# Main.net
KiCad netlist of a schematic drawn in Altium Designer
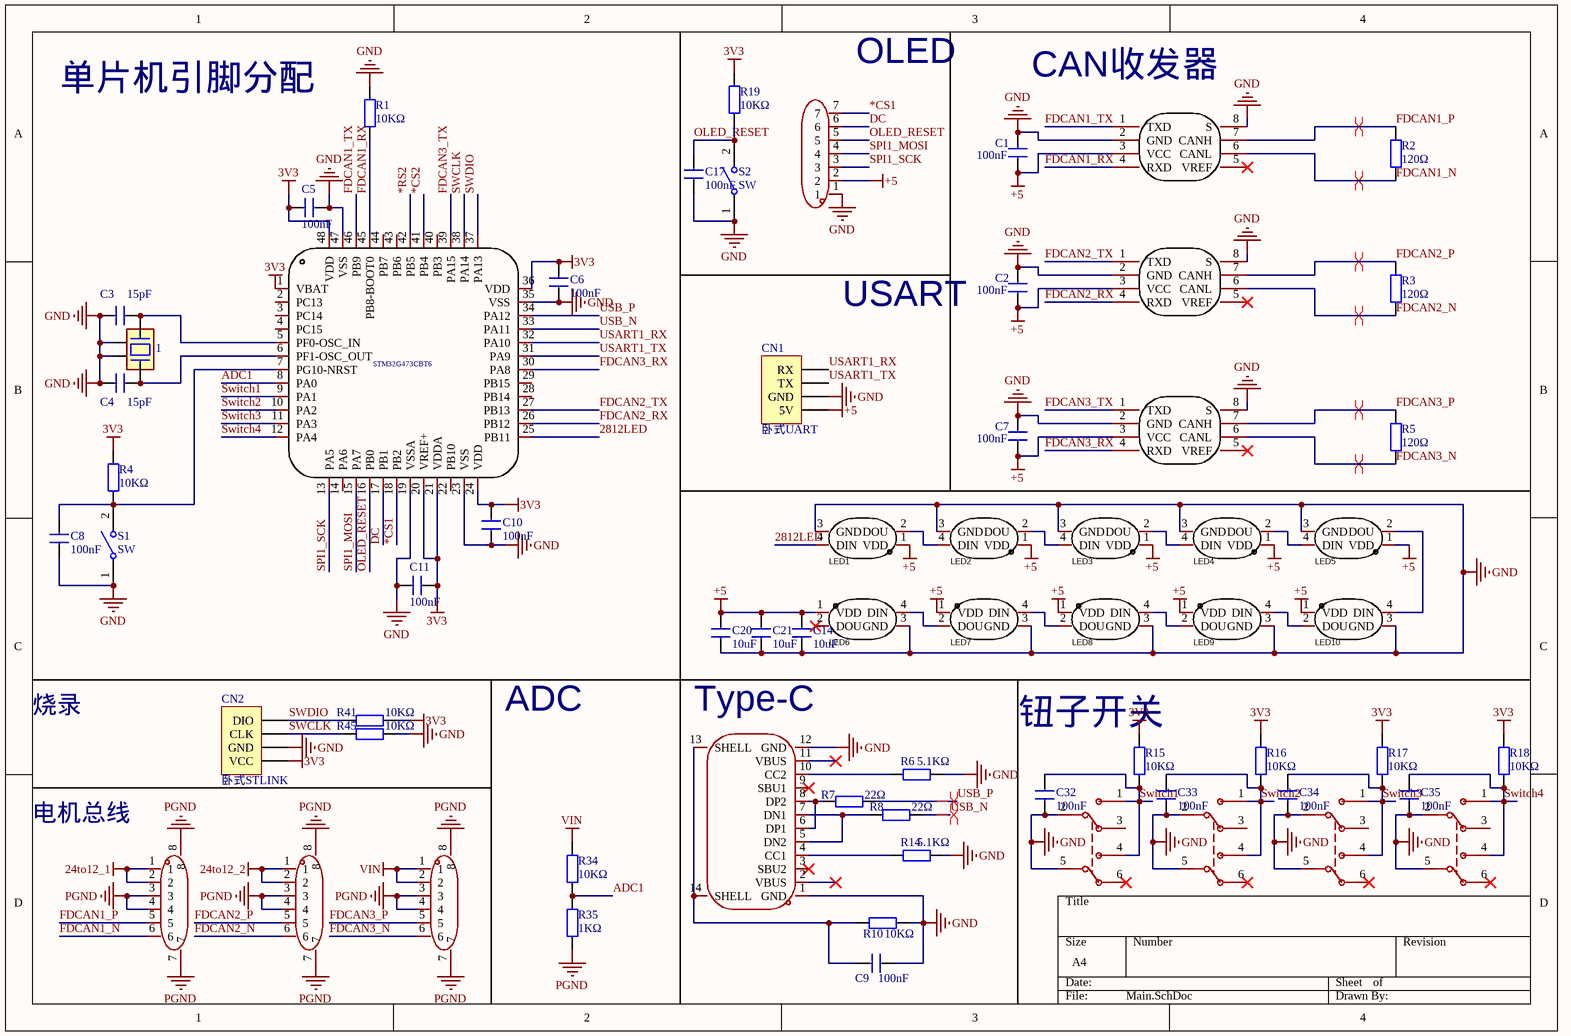
[diagram p0: Main.SchDoc]

(export (version "E")
  (design (tool "Eeschema 10.0.6"))
  (components
    (comp (ref "1")
      (value "3225贴片晶振")
      (footprint "OSC-3225-4P")
      (libsource (lib "Integrated_Library1") (part "3225贴片晶振"))
    )
    (comp (ref "C1")
      (value "100nF")
      (footprint "c0402")
      (description "贴片电容0402")
      (libsource (lib "Integrated_Library1") (part "0402贴片电容"))
    )
    (comp (ref "C2")
      (value "100nF")
      (footprint "c0402")
      (description "贴片电容0402")
      (libsource (lib "Integrated_Library1") (part "0402贴片电容"))
    )
    (comp (ref "C3")
      (value "15pF")
      (footprint "c0402")
      (description "贴片电容0402")
      (libsource (lib "Integrated_Library1") (part "0402贴片电容"))
    )
    (comp (ref "C4")
      (value "15pF")
      (footprint "c0402")
      (description "贴片电容0402")
      (libsource (lib "Integrated_Library1") (part "0402贴片电容"))
    )
    (comp (ref "C5")
      (value "100nF")
      (footprint "c0402")
      (description "贴片电容0402")
      (libsource (lib "Integrated_Library1") (part "0402贴片电容"))
    )
    (comp (ref "C6")
      (value "100nF")
      (footprint "c0402")
      (description "贴片电容0402")
      (libsource (lib "Integrated_Library1") (part "0402贴片电容"))
    )
    (comp (ref "C7")
      (value "100nF")
      (footprint "c0402")
      (description "贴片电容0402")
      (libsource (lib "Integrated_Library1") (part "0402贴片电容"))
    )
    (comp (ref "C8")
      (value "100nF")
      (footprint "c0402")
      (description "贴片电容0402")
      (libsource (lib "Integrated_Library1") (part "0402贴片电容"))
    )
    (comp (ref "C9")
      (value "100nF")
      (footprint "c0402")
      (description "贴片电容0402")
      (libsource (lib "Integrated_Library1") (part "0402贴片电容"))
    )
    (comp (ref "C10")
      (value "100nF")
      (footprint "c0402")
      (description "贴片电容0402")
      (libsource (lib "Integrated_Library1") (part "0402贴片电容"))
    )
    (comp (ref "C11")
      (value "100nF")
      (footprint "c0402")
      (description "贴片电容0402")
      (libsource (lib "Integrated_Library1") (part "0402贴片电容"))
    )
    (comp (ref "C14")
      (value "10uF")
      (footprint "1210")
      (description "1210贴片电容")
      (libsource (lib "Integrated_Library1") (part "1210贴片电容"))
    )
    (comp (ref "C17")
      (value "100nF")
      (footprint "c0402")
      (description "贴片电容0402")
      (libsource (lib "Integrated_Library1") (part "0402贴片电容"))
    )
    (comp (ref "C20")
      (value "10uF")
      (footprint "1210")
      (description "1210贴片电容")
      (libsource (lib "Integrated_Library1") (part "1210贴片电容"))
    )
    (comp (ref "C21")
      (value "10uF")
      (footprint "1210")
      (description "1210贴片电容")
      (libsource (lib "Integrated_Library1") (part "1210贴片电容"))
    )
    (comp (ref "C32")
      (value "100nF")
      (footprint "c0402")
      (description "贴片电容0402")
      (libsource (lib "Integrated_Library1") (part "0402贴片电容"))
    )
    (comp (ref "C33")
      (value "100nF")
      (footprint "c0402")
      (description "贴片电容0402")
      (libsource (lib "Integrated_Library1") (part "0402贴片电容"))
    )
    (comp (ref "C34")
      (value "100nF")
      (footprint "c0402")
      (description "贴片电容0402")
      (libsource (lib "Integrated_Library1") (part "0402贴片电容"))
    )
    (comp (ref "C35")
      (value "100nF")
      (footprint "c0402")
      (description "贴片电容0402")
      (libsource (lib "Integrated_Library1") (part "0402贴片电容"))
    )
    (comp (ref "CN1")
      (value "卧式UART")
      (footprint "CONN-SMD_4P-P1.25_GH1.25-4P")
      (libsource (lib "Integrated_Library1") (part "卧式UART"))
    )
    (comp (ref "CN2")
      (value "卧式STLINK")
      (footprint "CONN-SMD_4P-P1.25_GH1.25-4P")
      (libsource (lib "Integrated_Library1") (part "卧式STLINK"))
    )
    (comp (ref "H1")
      (value "PM254V-11-07-H85")
      (footprint "HDR-TH_7P-P2.54-V-F")
      (fields (field (name "MANUFACTURER") "XFCN(兴飞)"))
      (libsource (lib "Schlib1") (part "PM254V-11-07-H85"))
    )
    (comp (ref "LED1")
      (value "XL-5050RGBC-WS2812B")
      (footprint "LED-SMD_4P-L5.0-W5.0-BL_XL-5050RGBC")
      (description "WS2812B彩灯珠")
      (fields (field (name "MANUFACTURER") "XINGLIGHT(成兴光)"))
      (libsource (lib "RoBoMaster_AllComponent") (part "WS2812B彩灯珠"))
    )
    (comp (ref "LED2")
      (value "XL-5050RGBC-WS2812B")
      (footprint "LED-SMD_4P-L5.0-W5.0-BL_XL-5050RGBC")
      (description "WS2812B彩灯珠")
      (fields (field (name "MANUFACTURER") "XINGLIGHT(成兴光)"))
      (libsource (lib "RoBoMaster_AllComponent") (part "WS2812B彩灯珠"))
    )
    (comp (ref "LED3")
      (value "XL-5050RGBC-WS2812B")
      (footprint "LED-SMD_4P-L5.0-W5.0-BL_XL-5050RGBC")
      (description "WS2812B彩灯珠")
      (fields (field (name "MANUFACTURER") "XINGLIGHT(成兴光)"))
      (libsource (lib "RoBoMaster_AllComponent") (part "WS2812B彩灯珠"))
    )
    (comp (ref "LED4")
      (value "XL-5050RGBC-WS2812B")
      (footprint "LED-SMD_4P-L5.0-W5.0-BL_XL-5050RGBC")
      (description "WS2812B彩灯珠")
      (fields (field (name "MANUFACTURER") "XINGLIGHT(成兴光)"))
      (libsource (lib "RoBoMaster_AllComponent") (part "WS2812B彩灯珠"))
    )
    (comp (ref "LED5")
      (value "XL-5050RGBC-WS2812B")
      (footprint "LED-SMD_4P-L5.0-W5.0-BL_XL-5050RGBC")
      (description "WS2812B彩灯珠")
      (fields (field (name "MANUFACTURER") "XINGLIGHT(成兴光)"))
      (libsource (lib "RoBoMaster_AllComponent") (part "WS2812B彩灯珠"))
    )
    (comp (ref "LED6")
      (value "XL-5050RGBC-WS2812B")
      (footprint "LED-SMD_4P-L5.0-W5.0-BL_XL-5050RGBC")
      (description "WS2812B彩灯珠")
      (fields (field (name "MANUFACTURER") "XINGLIGHT(成兴光)"))
      (libsource (lib "RoBoMaster_AllComponent") (part "WS2812B彩灯珠"))
    )
    (comp (ref "LED7")
      (value "XL-5050RGBC-WS2812B")
      (footprint "LED-SMD_4P-L5.0-W5.0-BL_XL-5050RGBC")
      (description "WS2812B彩灯珠")
      (fields (field (name "MANUFACTURER") "XINGLIGHT(成兴光)"))
      (libsource (lib "RoBoMaster_AllComponent") (part "WS2812B彩灯珠"))
    )
    (comp (ref "LED8")
      (value "XL-5050RGBC-WS2812B")
      (footprint "LED-SMD_4P-L5.0-W5.0-BL_XL-5050RGBC")
      (description "WS2812B彩灯珠")
      (fields (field (name "MANUFACTURER") "XINGLIGHT(成兴光)"))
      (libsource (lib "RoBoMaster_AllComponent") (part "WS2812B彩灯珠"))
    )
    (comp (ref "LED9")
      (value "XL-5050RGBC-WS2812B")
      (footprint "LED-SMD_4P-L5.0-W5.0-BL_XL-5050RGBC")
      (description "WS2812B彩灯珠")
      (fields (field (name "MANUFACTURER") "XINGLIGHT(成兴光)"))
      (libsource (lib "RoBoMaster_AllComponent") (part "WS2812B彩灯珠"))
    )
    (comp (ref "LED10")
      (value "XL-5050RGBC-WS2812B")
      (footprint "LED-SMD_4P-L5.0-W5.0-BL_XL-5050RGBC")
      (description "WS2812B彩灯珠")
      (fields (field (name "MANUFACTURER") "XINGLIGHT(成兴光)"))
      (libsource (lib "RoBoMaster_AllComponent") (part "WS2812B彩灯珠"))
    )
    (comp (ref "R1")
      (value "10KΩ")
      (footprint "R0402")
      (description "0402贴片电阻")
      (libsource (lib "") (part "0402贴片电阻_3"))
    )
    (comp (ref "R2")
      (value "120Ω")
      (footprint "R0402")
      (description "0402贴片电阻")
      (libsource (lib "") (part "0402贴片电阻_1"))
    )
    (comp (ref "R3")
      (value "120Ω")
      (footprint "R0402")
      (description "0402贴片电阻")
      (libsource (lib "") (part "0402贴片电阻_1"))
    )
    (comp (ref "R4")
      (value "10KΩ")
      (footprint "R0402")
      (description "0402贴片电阻")
      (libsource (lib "") (part "0402贴片电阻_1"))
    )
    (comp (ref "R5")
      (value "120Ω")
      (footprint "R0402")
      (description "0402贴片电阻")
      (libsource (lib "") (part "0402贴片电阻_1"))
    )
    (comp (ref "R6")
      (value "5.1KΩ")
      (footprint "R0402")
      (description "0402贴片电阻")
      (libsource (lib "Integrated_Library1") (part "0402贴片电阻"))
    )
    (comp (ref "R7")
      (value "22Ω")
      (footprint "R0402")
      (description "0402贴片电阻")
      (libsource (lib "Integrated_Library1") (part "0402贴片电阻"))
    )
    (comp (ref "R8")
      (value "22Ω")
      (footprint "R0402")
      (description "0402贴片电阻")
      (libsource (lib "Integrated_Library1") (part "0402贴片电阻"))
    )
    (comp (ref "R10")
      (value "10KΩ")
      (footprint "R0402")
      (description "0402贴片电阻")
      (libsource (lib "Integrated_Library1") (part "0402贴片电阻"))
    )
    (comp (ref "R14")
      (value "5.1KΩ")
      (footprint "R0402")
      (description "0402贴片电阻")
      (libsource (lib "Integrated_Library1") (part "0402贴片电阻"))
    )
    (comp (ref "R15")
      (value "10KΩ")
      (footprint "R0402")
      (description "0402贴片电阻")
      (libsource (lib "") (part "0402贴片电阻_1"))
    )
    (comp (ref "R16")
      (value "10KΩ")
      (footprint "R0402")
      (description "0402贴片电阻")
      (libsource (lib "") (part "0402贴片电阻_1"))
    )
    (comp (ref "R17")
      (value "10KΩ")
      (footprint "R0402")
      (description "0402贴片电阻")
      (libsource (lib "") (part "0402贴片电阻_1"))
    )
    (comp (ref "R18")
      (value "10KΩ")
      (footprint "R0402")
      (description "0402贴片电阻")
      (libsource (lib "") (part "0402贴片电阻_1"))
    )
    (comp (ref "R19")
      (value "10KΩ")
      (footprint "R0402")
      (description "0402贴片电阻")
      (libsource (lib "") (part "0402贴片电阻_1"))
    )
    (comp (ref "R34")
      (value "10KΩ")
      (footprint "R0402")
      (description "0402贴片电阻")
      (libsource (lib "") (part "0402贴片电阻_2"))
    )
    (comp (ref "R35")
      (value "1KΩ")
      (footprint "R0402")
      (description "0402贴片电阻")
      (libsource (lib "") (part "0402贴片电阻_2"))
    )
    (comp (ref "R41")
      (value "10KΩ")
      (footprint "R0402")
      (description "0402贴片电阻")
      (libsource (lib "Integrated_Library1") (part "0402贴片电阻"))
    )
    (comp (ref "R45")
      (value "10KΩ")
      (footprint "R0402")
      (description "0402贴片电阻")
      (libsource (lib "Integrated_Library1") (part "0402贴片电阻"))
    )
    (comp (ref "S1")
      (value "SW")
      (footprint "KEY_SMD")
      (description "开关")
      (libsource (lib "Integrated_Library1") (part "SW"))
    )
    (comp (ref "S2")
      (value "SW")
      (footprint "KEY_SMD")
      (description "开关")
      (libsource (lib "Integrated_Library1") (part "SW"))
    )
    (comp (ref "U1")
      (value "ZX-ZH1.5-6PWT")
      (footprint "CONN-SMD_6P-P1.50_ZX-ZH1.5-6PWT")
      (fields (field (name "MANUFACTURER") "Megastar(兆星)"))
      (libsource (lib "Schlib1") (part "ZX-ZH1.5-6PWT"))
    )
    (comp (ref "U2")
      (value "SN65HVD1050DR")
      (footprint "SOIC-8_L4.9-W3.9-P1.27-LS6.0-BL")
      (description "CAN芯片")
      (fields (field (name "MANUFACTURER") "TI(德州仪器)"))
      (libsource (lib "Integrated_Library1") (part "SN65HVD1050DR"))
    )
    (comp (ref "U3")
      (value "ZX-ZH1.5-6PWT")
      (footprint "CONN-SMD_6P-P1.50_ZX-ZH1.5-6PWT")
      (fields (field (name "MANUFACTURER") "Megastar(兆星)"))
      (libsource (lib "Schlib1") (part "ZX-ZH1.5-6PWT"))
    )
    (comp (ref "U4")
      (value "STM32G474CET6")
      (footprint "LQFP-48")
      (fields (field (name "MANUFACTURER") "ST(意法半导体)") (field (name "MANUFACTURER PART") "STM32G473CBT6"))
      (libsource (lib "Integrated_Library1") (part "STM32G474CET6"))
    )
    (comp (ref "U5")
      (value "SN65HVD1050DR")
      (footprint "SOIC-8_L4.9-W3.9-P1.27-LS6.0-BL")
      (description "CAN芯片")
      (fields (field (name "MANUFACTURER") "TI(德州仪器)"))
      (libsource (lib "Integrated_Library1") (part "SN65HVD1050DR"))
    )
    (comp (ref "U6")
      (value "ZX-ZH1.5-6PWT")
      (footprint "CONN-SMD_6P-P1.50_ZX-ZH1.5-6PWT")
      (fields (field (name "MANUFACTURER") "Megastar(兆星)"))
      (libsource (lib "Schlib1") (part "ZX-ZH1.5-6PWT"))
    )
    (comp (ref "U8")
      (value "SN65HVD1050DR")
      (footprint "SOIC-8_L4.9-W3.9-P1.27-LS6.0-BL")
      (description "CAN芯片")
      (fields (field (name "MANUFACTURER") "TI(德州仪器)"))
      (libsource (lib "Integrated_Library1") (part "SN65HVD1050DR"))
    )
    (comp (ref "U9")
      (value "7208P1YZQI")
      (footprint "SW-TH_6P-L12.7-W11.4-P4.70-LS4.8")
      (fields (field (name "MANUFACTURER") "C&K"))
      (libsource (lib "Schlib1") (part "7208P1YZQI"))
    )
    (comp (ref "U10")
      (value "7208P1YZQI")
      (footprint "SW-TH_6P-L12.7-W11.4-P4.70-LS4.8")
      (fields (field (name "MANUFACTURER") "C&K"))
      (libsource (lib "Schlib1") (part "7208P1YZQI"))
    )
    (comp (ref "U11")
      (value "7208P1YZQI")
      (footprint "SW-TH_6P-L12.7-W11.4-P4.70-LS4.8")
      (fields (field (name "MANUFACTURER") "C&K"))
      (libsource (lib "Schlib1") (part "7208P1YZQI"))
    )
    (comp (ref "U12")
      (value "7208P1YZQI")
      (footprint "SW-TH_6P-L12.7-W11.4-P4.70-LS4.8")
      (fields (field (name "MANUFACTURER") "C&K"))
      (libsource (lib "Schlib1") (part "7208P1YZQI"))
    )
    (comp (ref "USB1")
      (value "TYPE-C 16PIN 2MD(073)")
      (footprint "USB-C-SMD_TYPE-C-6PIN-2MD-073")
      (fields (field (name "MANUFACTURER") "SHOU HAN(首韩)"))
      (libsource (lib "Schlib1") (part "TYPE-C 16PIN 2MD(073)"))
    )
  )
  (nets
    (net (code "1") (name "+5") (class "Default")
      (node (ref "C1") (pin "1") (pinfunction "1_1") (pintype "passive"))
      (node (ref "C14") (pin "2") (pinfunction "2_2") (pintype "passive"))
      (node (ref "C2") (pin "1") (pinfunction "1_1") (pintype "passive"))
      (node (ref "C20") (pin "2") (pinfunction "2_2") (pintype "passive"))
      (node (ref "C21") (pin "2") (pinfunction "2_2") (pintype "passive"))
      (node (ref "C7") (pin "1") (pinfunction "1_1") (pintype "passive"))
      (node (ref "CN1") (pin "1") (pinfunction "5V_1") (pintype "passive"))
      (node (ref "H1") (pin "2") (pinfunction "2_2") (pintype "passive"))
      (node (ref "LED1") (pin "1") (pinfunction "VDD_1") (pintype "passive"))
      (node (ref "LED10") (pin "1") (pinfunction "VDD_1") (pintype "passive"))
      (node (ref "LED2") (pin "1") (pinfunction "VDD_1") (pintype "passive"))
      (node (ref "LED3") (pin "1") (pinfunction "VDD_1") (pintype "passive"))
      (node (ref "LED4") (pin "1") (pinfunction "VDD_1") (pintype "passive"))
      (node (ref "LED5") (pin "1") (pinfunction "VDD_1") (pintype "passive"))
      (node (ref "LED6") (pin "1") (pinfunction "VDD_1") (pintype "passive"))
      (node (ref "LED7") (pin "1") (pinfunction "VDD_1") (pintype "passive"))
      (node (ref "LED8") (pin "1") (pinfunction "VDD_1") (pintype "passive"))
      (node (ref "LED9") (pin "1") (pinfunction "VDD_1") (pintype "passive"))
      (node (ref "U2") (pin "3") (pinfunction "VCC_3") (pintype "passive"))
      (node (ref "U5") (pin "3") (pinfunction "VCC_3") (pintype "passive"))
      (node (ref "U8") (pin "3") (pinfunction "VCC_3") (pintype "passive"))
    )
    (net (code "2") (name "/*CS1") (class "Default")
      (node (ref "H1") (pin "7") (pinfunction "7_7") (pintype "passive"))
      (node (ref "U4") (pin "18") (pinfunction "PB2_18") (pintype "passive"))
    )
    (net (code "3") (name "/*CS2") (class "Default")
      (node (ref "U4") (pin "41") (pinfunction "PB4_41") (pintype "passive"))
    )
    (net (code "4") (name "/*RS2") (class "Default")
      (node (ref "U4") (pin "42") (pinfunction "PB5_42") (pintype "passive"))
    )
    (net (code "5") (name "/2812LED") (class "Default")
      (node (ref "LED1") (pin "4") (pinfunction "DIN_4") (pintype "passive"))
      (node (ref "U4") (pin "25") (pinfunction "PB11_25") (pintype "passive"))
    )
    (net (code "6") (name "/ADC1") (class "Default")
      (node (ref "R34") (pin "1") (pinfunction "1_1") (pintype "passive"))
      (node (ref "R35") (pin "2") (pinfunction "2_2") (pintype "passive"))
      (node (ref "U4") (pin "8") (pinfunction "PA0_8") (pintype "passive"))
    )
    (net (code "7") (name "/DC") (class "Default")
      (node (ref "H1") (pin "6") (pinfunction "6_6") (pintype "passive"))
      (node (ref "U4") (pin "17") (pinfunction "PB1_17") (pintype "passive"))
    )
    (net (code "8") (name "/FDCAN1_N") (class "Default")
      (node (ref "R2") (pin "1") (pinfunction "1_1") (pintype "passive"))
      (node (ref "U1") (pin "6") (pinfunction "6_6") (pintype "passive"))
      (node (ref "U2") (pin "6") (pinfunction "CANL_6") (pintype "passive"))
    )
    (net (code "9") (name "/FDCAN1_P") (class "Default")
      (node (ref "R2") (pin "2") (pinfunction "2_2") (pintype "passive"))
      (node (ref "U1") (pin "5") (pinfunction "5_5") (pintype "passive"))
      (node (ref "U2") (pin "7") (pinfunction "CANH_7") (pintype "passive"))
    )
    (net (code "10") (name "/FDCAN1_RX") (class "Default")
      (node (ref "R1") (pin "2") (pinfunction "2_2") (pintype "passive"))
      (node (ref "U2") (pin "4") (pinfunction "RXD_4") (pintype "passive"))
      (node (ref "U4") (pin "45") (pinfunction "PB8-BOOT0_45") (pintype "passive"))
    )
    (net (code "11") (name "/FDCAN1_TX") (class "Default")
      (node (ref "U2") (pin "1") (pinfunction "TXD_1") (pintype "passive"))
      (node (ref "U4") (pin "46") (pinfunction "PB9_46") (pintype "passive"))
    )
    (net (code "12") (name "/FDCAN2_N") (class "Default")
      (node (ref "R3") (pin "1") (pinfunction "1_1") (pintype "passive"))
      (node (ref "U3") (pin "6") (pinfunction "6_6") (pintype "passive"))
      (node (ref "U5") (pin "6") (pinfunction "CANL_6") (pintype "passive"))
    )
    (net (code "13") (name "/FDCAN2_P") (class "Default")
      (node (ref "R3") (pin "2") (pinfunction "2_2") (pintype "passive"))
      (node (ref "U3") (pin "5") (pinfunction "5_5") (pintype "passive"))
      (node (ref "U5") (pin "7") (pinfunction "CANH_7") (pintype "passive"))
    )
    (net (code "14") (name "/FDCAN2_RX") (class "Default")
      (node (ref "U4") (pin "26") (pinfunction "PB12_26") (pintype "passive"))
      (node (ref "U5") (pin "4") (pinfunction "RXD_4") (pintype "passive"))
    )
    (net (code "15") (name "/FDCAN2_TX") (class "Default")
      (node (ref "U4") (pin "27") (pinfunction "PB13_27") (pintype "passive"))
      (node (ref "U5") (pin "1") (pinfunction "TXD_1") (pintype "passive"))
    )
    (net (code "16") (name "/FDCAN3_N") (class "Default")
      (node (ref "R5") (pin "1") (pinfunction "1_1") (pintype "passive"))
      (node (ref "U6") (pin "6") (pinfunction "6_6") (pintype "passive"))
      (node (ref "U8") (pin "6") (pinfunction "CANL_6") (pintype "passive"))
    )
    (net (code "17") (name "/FDCAN3_P") (class "Default")
      (node (ref "R5") (pin "2") (pinfunction "2_2") (pintype "passive"))
      (node (ref "U6") (pin "5") (pinfunction "5_5") (pintype "passive"))
      (node (ref "U8") (pin "7") (pinfunction "CANH_7") (pintype "passive"))
    )
    (net (code "18") (name "/FDCAN3_RX") (class "Default")
      (node (ref "U4") (pin "30") (pinfunction "PA8_30") (pintype "passive"))
      (node (ref "U8") (pin "4") (pinfunction "RXD_4") (pintype "passive"))
    )
    (net (code "19") (name "/FDCAN3_TX") (class "Default")
      (node (ref "U4") (pin "39") (pinfunction "PA15_39") (pintype "passive"))
      (node (ref "U8") (pin "1") (pinfunction "TXD_1") (pintype "passive"))
    )
    (net (code "20") (name "/OLED_RESET") (class "Default")
      (node (ref "C17") (pin "2") (pinfunction "2_2") (pintype "passive"))
      (node (ref "H1") (pin "5") (pinfunction "5_5") (pintype "passive"))
      (node (ref "R19") (pin "1") (pinfunction "1_1") (pintype "passive"))
      (node (ref "S2") (pin "2") (pinfunction "NO_2") (pintype "passive"))
      (node (ref "U4") (pin "16") (pinfunction "PB0_16") (pintype "passive"))
    )
    (net (code "21") (name "/SPI1_MOSI") (class "Default")
      (node (ref "H1") (pin "4") (pinfunction "4_4") (pintype "passive"))
      (node (ref "U4") (pin "15") (pinfunction "PA7_15") (pintype "passive"))
    )
    (net (code "22") (name "/SPI1_SCK") (class "Default")
      (node (ref "H1") (pin "3") (pinfunction "3_3") (pintype "passive"))
      (node (ref "U4") (pin "13") (pinfunction "PA5_13") (pintype "passive"))
    )
    (net (code "23") (name "/SWCLK") (class "Default")
      (node (ref "CN2") (pin "3") (pinfunction "CLK_3") (pintype "passive"))
      (node (ref "R45") (pin "1") (pinfunction "1_1") (pintype "passive"))
      (node (ref "U4") (pin "38") (pinfunction "PA14_38") (pintype "passive"))
    )
    (net (code "24") (name "/SWDIO") (class "Default")
      (node (ref "CN2") (pin "4") (pinfunction "DIO_4") (pintype "passive"))
      (node (ref "R41") (pin "1") (pinfunction "1_1") (pintype "passive"))
      (node (ref "U4") (pin "37") (pinfunction "PA13_37") (pintype "passive"))
    )
    (net (code "25") (name "/Switch1") (class "Default")
      (node (ref "C32") (pin "2") (pinfunction "2_2") (pintype "passive"))
      (node (ref "R15") (pin "1") (pinfunction "1_1") (pintype "passive"))
      (node (ref "U4") (pin "9") (pinfunction "PA1_9") (pintype "passive"))
      (node (ref "U9") (pin "1") (pinfunction "1_1") (pintype "passive"))
      (node (ref "U9") (pin "4") (pinfunction "4_4") (pintype "passive"))
    )
    (net (code "26") (name "/Switch2") (class "Default")
      (node (ref "C33") (pin "2") (pinfunction "2_2") (pintype "passive"))
      (node (ref "R16") (pin "1") (pinfunction "1_1") (pintype "passive"))
      (node (ref "U10") (pin "1") (pinfunction "1_1") (pintype "passive"))
      (node (ref "U10") (pin "4") (pinfunction "4_4") (pintype "passive"))
      (node (ref "U4") (pin "10") (pinfunction "PA2_10") (pintype "passive"))
    )
    (net (code "27") (name "/Switch3") (class "Default")
      (node (ref "C34") (pin "2") (pinfunction "2_2") (pintype "passive"))
      (node (ref "R17") (pin "1") (pinfunction "1_1") (pintype "passive"))
      (node (ref "U11") (pin "1") (pinfunction "1_1") (pintype "passive"))
      (node (ref "U11") (pin "4") (pinfunction "4_4") (pintype "passive"))
      (node (ref "U4") (pin "11") (pinfunction "PA3_11") (pintype "passive"))
    )
    (net (code "28") (name "/Switch4") (class "Default")
      (node (ref "C35") (pin "2") (pinfunction "2_2") (pintype "passive"))
      (node (ref "R18") (pin "1") (pinfunction "1_1") (pintype "passive"))
      (node (ref "U12") (pin "1") (pinfunction "1_1") (pintype "passive"))
      (node (ref "U12") (pin "4") (pinfunction "4_4") (pintype "passive"))
      (node (ref "U4") (pin "12") (pinfunction "PA4_12") (pintype "passive"))
    )
    (net (code "29") (name "/USART1_RX") (class "Default")
      (node (ref "CN1") (pin "4") (pinfunction "RX_4") (pintype "passive"))
      (node (ref "U4") (pin "32") (pinfunction "PA10_32") (pintype "passive"))
    )
    (net (code "30") (name "/USART1_TX") (class "Default")
      (node (ref "CN1") (pin "3") (pinfunction "TX_3") (pintype "passive"))
      (node (ref "U4") (pin "31") (pinfunction "PA9_31") (pintype "passive"))
    )
    (net (code "31") (name "/USB_N") (class "Default")
      (node (ref "R8") (pin "2") (pinfunction "2_2") (pintype "passive"))
      (node (ref "U4") (pin "33") (pinfunction "PA11_33") (pintype "passive"))
    )
    (net (code "32") (name "/USB_P") (class "Default")
      (node (ref "R7") (pin "2") (pinfunction "2_2") (pintype "passive"))
      (node (ref "U4") (pin "34") (pinfunction "PA12_34") (pintype "passive"))
    )
    (net (code "33") (name "3V3") (class "Default")
      (node (ref "C10") (pin "2") (pinfunction "2_2") (pintype "passive"))
      (node (ref "C11") (pin "1") (pinfunction "1_1") (pintype "passive"))
      (node (ref "C5") (pin "2") (pinfunction "2_2") (pintype "passive"))
      (node (ref "C6") (pin "2") (pinfunction "2_2") (pintype "passive"))
      (node (ref "CN2") (pin "1") (pinfunction "VCC_1") (pintype "passive"))
      (node (ref "R15") (pin "2") (pinfunction "2_2") (pintype "passive"))
      (node (ref "R16") (pin "2") (pinfunction "2_2") (pintype "passive"))
      (node (ref "R17") (pin "2") (pinfunction "2_2") (pintype "passive"))
      (node (ref "R18") (pin "2") (pinfunction "2_2") (pintype "passive"))
      (node (ref "R19") (pin "2") (pinfunction "2_2") (pintype "passive"))
      (node (ref "R4") (pin "2") (pinfunction "2_2") (pintype "passive"))
      (node (ref "R41") (pin "2") (pinfunction "2_2") (pintype "passive"))
      (node (ref "U4") (pin "1") (pinfunction "VBAT_1") (pintype "passive"))
      (node (ref "U4") (pin "20") (pinfunction "VREF+_20") (pintype "passive"))
      (node (ref "U4") (pin "21") (pinfunction "VDDA_21") (pintype "passive"))
      (node (ref "U4") (pin "24") (pinfunction "VDD_24") (pintype "passive"))
      (node (ref "U4") (pin "36") (pinfunction "VDD_36") (pintype "passive"))
      (node (ref "U4") (pin "48") (pinfunction "VDD_48") (pintype "passive"))
    )
    (net (code "34") (name "24to12_1") (class "Default")
      (node (ref "U1") (pin "1") (pinfunction "1_1") (pintype "passive"))
      (node (ref "U1") (pin "2") (pinfunction "2_2") (pintype "passive"))
    )
    (net (code "35") (name "24to12_2") (class "Default")
      (node (ref "U3") (pin "1") (pinfunction "1_1") (pintype "passive"))
      (node (ref "U3") (pin "2") (pinfunction "2_2") (pintype "passive"))
    )
    (net (code "36") (name "GND") (class "Default")
      (node (ref "1") (pin "2") (pinfunction "2_2") (pintype "passive"))
      (node (ref "1") (pin "4") (pinfunction "4_4") (pintype "passive"))
      (node (ref "C1") (pin "2") (pinfunction "2_2") (pintype "passive"))
      (node (ref "C10") (pin "1") (pinfunction "1_1") (pintype "passive"))
      (node (ref "C11") (pin "2") (pinfunction "2_2") (pintype "passive"))
      (node (ref "C14") (pin "1") (pinfunction "1_1") (pintype "passive"))
      (node (ref "C17") (pin "1") (pinfunction "1_1") (pintype "passive"))
      (node (ref "C2") (pin "2") (pinfunction "2_2") (pintype "passive"))
      (node (ref "C20") (pin "1") (pinfunction "1_1") (pintype "passive"))
      (node (ref "C21") (pin "1") (pinfunction "1_1") (pintype "passive"))
      (node (ref "C3") (pin "1") (pinfunction "1_1") (pintype "passive"))
      (node (ref "C32") (pin "1") (pinfunction "1_1") (pintype "passive"))
      (node (ref "C33") (pin "1") (pinfunction "1_1") (pintype "passive"))
      (node (ref "C34") (pin "1") (pinfunction "1_1") (pintype "passive"))
      (node (ref "C35") (pin "1") (pinfunction "1_1") (pintype "passive"))
      (node (ref "C4") (pin "1") (pinfunction "1_1") (pintype "passive"))
      (node (ref "C5") (pin "1") (pinfunction "1_1") (pintype "passive"))
      (node (ref "C6") (pin "1") (pinfunction "1_1") (pintype "passive"))
      (node (ref "C7") (pin "2") (pinfunction "2_2") (pintype "passive"))
      (node (ref "C8") (pin "1") (pinfunction "1_1") (pintype "passive"))
      (node (ref "C9") (pin "2") (pinfunction "2_2") (pintype "passive"))
      (node (ref "CN1") (pin "2") (pinfunction "GND_2") (pintype "passive"))
      (node (ref "CN2") (pin "2") (pinfunction "GND_2") (pintype "passive"))
      (node (ref "H1") (pin "1") (pinfunction "1_1") (pintype "passive"))
      (node (ref "LED1") (pin "3") (pinfunction "GND_3") (pintype "passive"))
      (node (ref "LED10") (pin "3") (pinfunction "GND_3") (pintype "passive"))
      (node (ref "LED2") (pin "3") (pinfunction "GND_3") (pintype "passive"))
      (node (ref "LED3") (pin "3") (pinfunction "GND_3") (pintype "passive"))
      (node (ref "LED4") (pin "3") (pinfunction "GND_3") (pintype "passive"))
      (node (ref "LED5") (pin "3") (pinfunction "GND_3") (pintype "passive"))
      (node (ref "LED6") (pin "3") (pinfunction "GND_3") (pintype "passive"))
      (node (ref "LED7") (pin "3") (pinfunction "GND_3") (pintype "passive"))
      (node (ref "LED8") (pin "3") (pinfunction "GND_3") (pintype "passive"))
      (node (ref "LED9") (pin "3") (pinfunction "GND_3") (pintype "passive"))
      (node (ref "R1") (pin "1") (pinfunction "1_1") (pintype "passive"))
      (node (ref "R10") (pin "2") (pinfunction "2_2") (pintype "passive"))
      (node (ref "R14") (pin "2") (pinfunction "2_2") (pintype "passive"))
      (node (ref "R45") (pin "2") (pinfunction "2_2") (pintype "passive"))
      (node (ref "R6") (pin "2") (pinfunction "2_2") (pintype "passive"))
      (node (ref "S1") (pin "1") (pinfunction "COMMON_1") (pintype "passive"))
      (node (ref "S2") (pin "1") (pinfunction "COMMON_1") (pintype "passive"))
      (node (ref "U10") (pin "2") (pinfunction "2_2") (pintype "passive"))
      (node (ref "U10") (pin "5") (pinfunction "5_5") (pintype "passive"))
      (node (ref "U11") (pin "2") (pinfunction "2_2") (pintype "passive"))
      (node (ref "U11") (pin "5") (pinfunction "5_5") (pintype "passive"))
      (node (ref "U12") (pin "2") (pinfunction "2_2") (pintype "passive"))
      (node (ref "U12") (pin "5") (pinfunction "5_5") (pintype "passive"))
      (node (ref "U2") (pin "2") (pinfunction "GND_2") (pintype "passive"))
      (node (ref "U2") (pin "8") (pinfunction "S_8") (pintype "passive"))
      (node (ref "U4") (pin "19") (pinfunction "VSSA_19") (pintype "passive"))
      (node (ref "U4") (pin "23") (pinfunction "VSS_23") (pintype "passive"))
      (node (ref "U4") (pin "35") (pinfunction "VSS_35") (pintype "passive"))
      (node (ref "U4") (pin "47") (pinfunction "VSS_47") (pintype "passive"))
      (node (ref "U5") (pin "2") (pinfunction "GND_2") (pintype "passive"))
      (node (ref "U5") (pin "8") (pinfunction "S_8") (pintype "passive"))
      (node (ref "U8") (pin "2") (pinfunction "GND_2") (pintype "passive"))
      (node (ref "U8") (pin "8") (pinfunction "S_8") (pintype "passive"))
      (node (ref "U9") (pin "2") (pinfunction "2_2") (pintype "passive"))
      (node (ref "U9") (pin "5") (pinfunction "5_5") (pintype "passive"))
      (node (ref "USB1") (pin "1") (pinfunction "GND_1") (pintype "passive"))
      (node (ref "USB1") (pin "12") (pinfunction "GND_12") (pintype "passive"))
    )
    (net (code "37") (name "Net-(C9-Pad1)") (class "Default")
      (node (ref "C9") (pin "1") (pinfunction "1_1") (pintype "passive"))
      (node (ref "R10") (pin "1") (pinfunction "1_1") (pintype "passive"))
      (node (ref "USB1") (pin "13") (pinfunction "SHELL_13") (pintype "passive"))
      (node (ref "USB1") (pin "14") (pinfunction "SHELL_14") (pintype "passive"))
    )
    (net (code "38") (name "Net-(LED1-DOU)") (class "Default")
      (node (ref "LED1") (pin "2") (pinfunction "DOU_2") (pintype "passive"))
      (node (ref "LED2") (pin "4") (pinfunction "DIN_4") (pintype "passive"))
    )
    (net (code "39") (name "Net-(LED2-DOU)") (class "Default")
      (node (ref "LED2") (pin "2") (pinfunction "DOU_2") (pintype "passive"))
      (node (ref "LED3") (pin "4") (pinfunction "DIN_4") (pintype "passive"))
    )
    (net (code "40") (name "Net-(LED3-DOU)") (class "Default")
      (node (ref "LED3") (pin "2") (pinfunction "DOU_2") (pintype "passive"))
      (node (ref "LED4") (pin "4") (pinfunction "DIN_4") (pintype "passive"))
    )
    (net (code "41") (name "Net-(LED4-DOU)") (class "Default")
      (node (ref "LED4") (pin "2") (pinfunction "DOU_2") (pintype "passive"))
      (node (ref "LED5") (pin "4") (pinfunction "DIN_4") (pintype "passive"))
    )
    (net (code "42") (name "Net-(LED6-DIN)") (class "Default")
      (node (ref "LED6") (pin "4") (pinfunction "DIN_4") (pintype "passive"))
      (node (ref "LED7") (pin "2") (pinfunction "DOU_2") (pintype "passive"))
    )
    (net (code "43") (name "Net-(LED7-DIN)") (class "Default")
      (node (ref "LED7") (pin "4") (pinfunction "DIN_4") (pintype "passive"))
      (node (ref "LED8") (pin "2") (pinfunction "DOU_2") (pintype "passive"))
    )
    (net (code "44") (name "Net-(LED8-DIN)") (class "Default")
      (node (ref "LED8") (pin "4") (pinfunction "DIN_4") (pintype "passive"))
      (node (ref "LED9") (pin "2") (pinfunction "DOU_2") (pintype "passive"))
    )
    (net (code "45") (name "Net-(LED10-DIN)") (class "Default")
      (node (ref "LED10") (pin "4") (pinfunction "DIN_4") (pintype "passive"))
      (node (ref "LED5") (pin "2") (pinfunction "DOU_2") (pintype "passive"))
    )
    (net (code "46") (name "Net-(LED10-DOU)") (class "Default")
      (node (ref "LED10") (pin "2") (pinfunction "DOU_2") (pintype "passive"))
      (node (ref "LED9") (pin "4") (pinfunction "DIN_4") (pintype "passive"))
    )
    (net (code "47") (name "Net-(S1-NO)") (class "Default")
      (node (ref "C8") (pin "2") (pinfunction "2_2") (pintype "passive"))
      (node (ref "R4") (pin "1") (pinfunction "1_1") (pintype "passive"))
      (node (ref "S1") (pin "2") (pinfunction "NO_2") (pintype "passive"))
      (node (ref "U4") (pin "7") (pinfunction "PG10-NRST_7") (pintype "passive"))
    )
    (net (code "48") (name "Net-(U4-PF0-OSC_IN)") (class "Default")
      (node (ref "1") (pin "3") (pinfunction "3_3") (pintype "passive"))
      (node (ref "C3") (pin "2") (pinfunction "2_2") (pintype "passive"))
      (node (ref "U4") (pin "5") (pinfunction "PF0-OSC_IN_5") (pintype "passive"))
    )
    (net (code "49") (name "Net-(U4-PF1-OSC_OUT)") (class "Default")
      (node (ref "1") (pin "1") (pinfunction "1_1") (pintype "passive"))
      (node (ref "C4") (pin "2") (pinfunction "2_2") (pintype "passive"))
      (node (ref "U4") (pin "6") (pinfunction "PF1-OSC_OUT_6") (pintype "passive"))
    )
    (net (code "50") (name "Net-(USB1-CC1)") (class "Default")
      (node (ref "R14") (pin "1") (pinfunction "1_1") (pintype "passive"))
      (node (ref "USB1") (pin "4") (pinfunction "CC1_4") (pintype "passive"))
    )
    (net (code "51") (name "Net-(USB1-CC2)") (class "Default")
      (node (ref "R6") (pin "1") (pinfunction "1_1") (pintype "passive"))
      (node (ref "USB1") (pin "10") (pinfunction "CC2_10") (pintype "passive"))
    )
    (net (code "52") (name "Net-(USB1-DN1)") (class "Default")
      (node (ref "R8") (pin "1") (pinfunction "1_1") (pintype "passive"))
      (node (ref "USB1") (pin "5") (pinfunction "DN2_5") (pintype "passive"))
      (node (ref "USB1") (pin "7") (pinfunction "DN1_7") (pintype "passive"))
    )
    (net (code "53") (name "Net-(USB1-DP1)") (class "Default")
      (node (ref "R7") (pin "1") (pinfunction "1_1") (pintype "passive"))
      (node (ref "USB1") (pin "6") (pinfunction "DP1_6") (pintype "passive"))
      (node (ref "USB1") (pin "8") (pinfunction "DP2_8") (pintype "passive"))
    )
    (net (code "54") (name "PGND") (class "Default")
      (node (ref "R35") (pin "1") (pinfunction "1_1") (pintype "passive"))
      (node (ref "U1") (pin "3") (pinfunction "3_3") (pintype "passive"))
      (node (ref "U1") (pin "4") (pinfunction "4_4") (pintype "passive"))
      (node (ref "U1") (pin "7") (pinfunction "7_7") (pintype "passive"))
      (node (ref "U1") (pin "8") (pinfunction "8_8") (pintype "passive"))
      (node (ref "U3") (pin "3") (pinfunction "3_3") (pintype "passive"))
      (node (ref "U3") (pin "4") (pinfunction "4_4") (pintype "passive"))
      (node (ref "U3") (pin "7") (pinfunction "7_7") (pintype "passive"))
      (node (ref "U3") (pin "8") (pinfunction "8_8") (pintype "passive"))
      (node (ref "U6") (pin "3") (pinfunction "3_3") (pintype "passive"))
      (node (ref "U6") (pin "4") (pinfunction "4_4") (pintype "passive"))
      (node (ref "U6") (pin "7") (pinfunction "7_7") (pintype "passive"))
      (node (ref "U6") (pin "8") (pinfunction "8_8") (pintype "passive"))
    )
    (net (code "55") (name "VIN") (class "Default")
      (node (ref "R34") (pin "2") (pinfunction "2_2") (pintype "passive"))
      (node (ref "U6") (pin "1") (pinfunction "1_1") (pintype "passive"))
      (node (ref "U6") (pin "2") (pinfunction "2_2") (pintype "passive"))
    )
    (net (code "56") (name "unconnected-(LED6-DOU-Pad2)") (class "Default")
      (node (ref "LED6") (pin "2") (pinfunction "DOU_2") (pintype "passive+no_connect"))
    )
    (net (code "57") (name "unconnected-(U2-VREF-Pad5)") (class "Default")
      (node (ref "U2") (pin "5") (pinfunction "VREF_5") (pintype "passive+no_connect"))
    )
    (net (code "58") (name "unconnected-(U4-PA6-Pad14)") (class "Default")
      (node (ref "U4") (pin "14") (pinfunction "PA6_14") (pintype "passive"))
    )
    (net (code "59") (name "unconnected-(U4-PB3-Pad40)") (class "Default")
      (node (ref "U4") (pin "40") (pinfunction "PB3_40") (pintype "passive"))
    )
    (net (code "60") (name "unconnected-(U4-PB6-Pad43)") (class "Default")
      (node (ref "U4") (pin "43") (pinfunction "PB6_43") (pintype "passive"))
    )
    (net (code "61") (name "unconnected-(U4-PB7-Pad44)") (class "Default")
      (node (ref "U4") (pin "44") (pinfunction "PB7_44") (pintype "passive"))
    )
    (net (code "62") (name "unconnected-(U4-PB10-Pad22)") (class "Default")
      (node (ref "U4") (pin "22") (pinfunction "PB10_22") (pintype "passive"))
    )
    (net (code "63") (name "unconnected-(U4-PB14-Pad28)") (class "Default")
      (node (ref "U4") (pin "28") (pinfunction "PB14_28") (pintype "passive"))
    )
    (net (code "64") (name "unconnected-(U4-PB15-Pad29)") (class "Default")
      (node (ref "U4") (pin "29") (pinfunction "PB15_29") (pintype "passive"))
    )
    (net (code "65") (name "unconnected-(U4-PC13-Pad2)") (class "Default")
      (node (ref "U4") (pin "2") (pinfunction "PC13_2") (pintype "passive"))
    )
    (net (code "66") (name "unconnected-(U4-PC14-Pad3)") (class "Default")
      (node (ref "U4") (pin "3") (pinfunction "PC14_3") (pintype "passive"))
    )
    (net (code "67") (name "unconnected-(U4-PC15-Pad4)") (class "Default")
      (node (ref "U4") (pin "4") (pinfunction "PC15_4") (pintype "passive"))
    )
    (net (code "68") (name "unconnected-(U5-VREF-Pad5)") (class "Default")
      (node (ref "U5") (pin "5") (pinfunction "VREF_5") (pintype "passive+no_connect"))
    )
    (net (code "69") (name "unconnected-(U8-VREF-Pad5)") (class "Default")
      (node (ref "U8") (pin "5") (pinfunction "VREF_5") (pintype "passive+no_connect"))
    )
    (net (code "70") (name "unconnected-(U9-Pad3)") (class "Default")
      (node (ref "U9") (pin "3") (pinfunction "3_3") (pintype "passive"))
    )
    (net (code "71") (name "unconnected-(U9-Pad6)") (class "Default")
      (node (ref "U9") (pin "6") (pinfunction "6_6") (pintype "passive+no_connect"))
    )
    (net (code "72") (name "unconnected-(U10-Pad3)") (class "Default")
      (node (ref "U10") (pin "3") (pinfunction "3_3") (pintype "passive"))
    )
    (net (code "73") (name "unconnected-(U10-Pad6)") (class "Default")
      (node (ref "U10") (pin "6") (pinfunction "6_6") (pintype "passive+no_connect"))
    )
    (net (code "74") (name "unconnected-(U11-Pad3)") (class "Default")
      (node (ref "U11") (pin "3") (pinfunction "3_3") (pintype "passive"))
    )
    (net (code "75") (name "unconnected-(U11-Pad6)") (class "Default")
      (node (ref "U11") (pin "6") (pinfunction "6_6") (pintype "passive+no_connect"))
    )
    (net (code "76") (name "unconnected-(U12-Pad3)") (class "Default")
      (node (ref "U12") (pin "3") (pinfunction "3_3") (pintype "passive"))
    )
    (net (code "77") (name "unconnected-(U12-Pad6)") (class "Default")
      (node (ref "U12") (pin "6") (pinfunction "6_6") (pintype "passive+no_connect"))
    )
    (net (code "78") (name "unconnected-(USB1-SBU1-Pad9)") (class "Default")
      (node (ref "USB1") (pin "9") (pinfunction "SBU1_9") (pintype "passive+no_connect"))
    )
    (net (code "79") (name "unconnected-(USB1-SBU2-Pad3)") (class "Default")
      (node (ref "USB1") (pin "3") (pinfunction "SBU2_3") (pintype "passive+no_connect"))
    )
    (net (code "80") (name "unconnected-(USB1-VBUS-Pad2)") (class "Default")
      (node (ref "USB1") (pin "2") (pinfunction "VBUS_2") (pintype "passive+no_connect"))
    )
    (net (code "81") (name "unconnected-(USB1-VBUS-Pad11)") (class "Default")
      (node (ref "USB1") (pin "11") (pinfunction "VBUS_11") (pintype "passive+no_connect"))
    )
  )
)
